# PSU.net
KiCad netlist of a schematic drawn in EAGLE
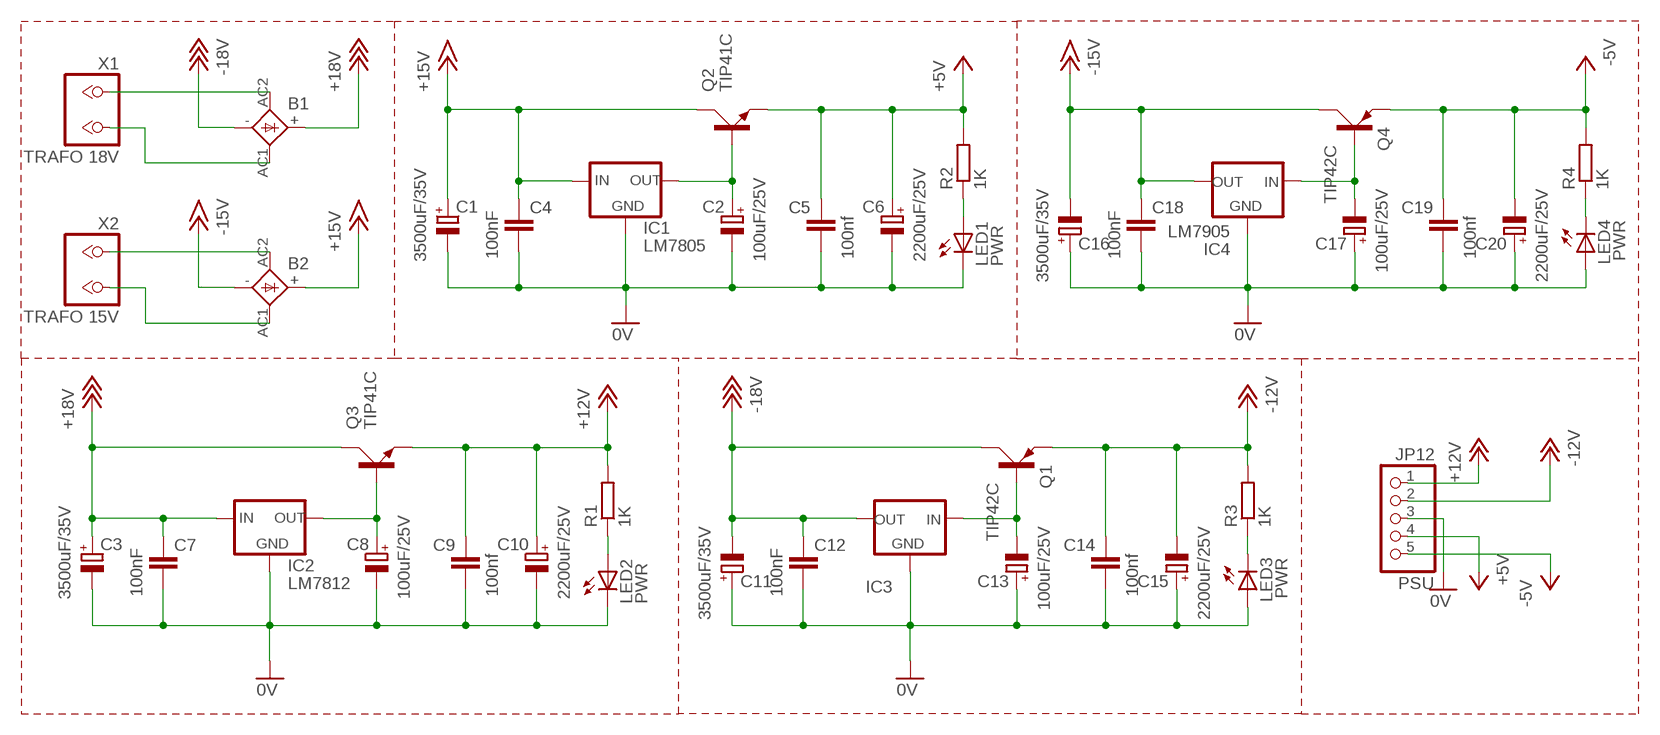
[diagram p0: schematic, sheet 1]

(export (version "E")
  (design (tool "Eeschema 10.0.6"))
  (components
    (comp (ref "B1")
      (value "KBL")
      (footprint "eagle-import:KBL")
      (libsource (lib "eagle-import") (part "KBL"))
    )
    (comp (ref "B2")
      (value "KBL")
      (footprint "eagle-import:KBL")
      (libsource (lib "eagle-import") (part "KBL"))
    )
    (comp (ref "C1")
      (value "3500uF/35V")
      (footprint "eagle-import:EB20D")
      (libsource (lib "eagle-import") (part "CPOL-EUE10-20"))
    )
    (comp (ref "C2")
      (value "100uF/25V")
      (footprint "eagle-import:E2,5-7")
      (libsource (lib "eagle-import") (part "CPOL-EUE2.5-7"))
    )
    (comp (ref "C3")
      (value "3500uF/35V")
      (footprint "eagle-import:EB20D")
      (libsource (lib "eagle-import") (part "CPOL-EUE10-20"))
    )
    (comp (ref "C4")
      (value "100nF")
      (footprint "eagle-import:C050-025X075")
      (libsource (lib "eagle-import") (part "C-EU050-025X075"))
    )
    (comp (ref "C5")
      (value "100nf")
      (footprint "eagle-import:C050-025X075")
      (libsource (lib "eagle-import") (part "C-EU050-025X075"))
    )
    (comp (ref "C6")
      (value "2200uF/25V")
      (footprint "eagle-import:E5-13")
      (libsource (lib "eagle-import") (part "CPOL-EUE5-13"))
    )
    (comp (ref "C7")
      (value "100nF")
      (footprint "eagle-import:C050-025X075")
      (libsource (lib "eagle-import") (part "C-EU050-025X075"))
    )
    (comp (ref "C8")
      (value "100uF/25V")
      (footprint "eagle-import:E2,5-7")
      (libsource (lib "eagle-import") (part "CPOL-EUE2.5-7"))
    )
    (comp (ref "C9")
      (value "100nf")
      (footprint "eagle-import:C050-025X075")
      (libsource (lib "eagle-import") (part "C-EU050-025X075"))
    )
    (comp (ref "C10")
      (value "2200uF/25V")
      (footprint "eagle-import:E5-13")
      (libsource (lib "eagle-import") (part "CPOL-EUE5-13"))
    )
    (comp (ref "C11")
      (value "3500uF/35V")
      (footprint "eagle-import:EB20D")
      (libsource (lib "eagle-import") (part "CPOL-EUE10-20"))
    )
    (comp (ref "C12")
      (value "100nF")
      (footprint "eagle-import:C050-025X075")
      (libsource (lib "eagle-import") (part "C-EU050-025X075"))
    )
    (comp (ref "C13")
      (value "100uF/25V")
      (footprint "eagle-import:E2,5-7")
      (libsource (lib "eagle-import") (part "CPOL-EUE2.5-7"))
    )
    (comp (ref "C14")
      (value "100nf")
      (footprint "eagle-import:C050-025X075")
      (libsource (lib "eagle-import") (part "C-EU050-025X075"))
    )
    (comp (ref "C15")
      (value "2200uF/25V")
      (footprint "eagle-import:E5-13")
      (libsource (lib "eagle-import") (part "CPOL-EUE5-13"))
    )
    (comp (ref "C16")
      (value "3500uF/35V")
      (footprint "eagle-import:EB20D")
      (libsource (lib "eagle-import") (part "CPOL-EUE10-20"))
    )
    (comp (ref "C17")
      (value "100uF/25V")
      (footprint "eagle-import:E2,5-7")
      (libsource (lib "eagle-import") (part "CPOL-EUE2.5-7"))
    )
    (comp (ref "C18")
      (value "100nF")
      (footprint "eagle-import:C050-025X075")
      (libsource (lib "eagle-import") (part "C-EU050-025X075"))
    )
    (comp (ref "C19")
      (value "100nf")
      (footprint "eagle-import:C050-025X075")
      (libsource (lib "eagle-import") (part "C-EU050-025X075"))
    )
    (comp (ref "C20")
      (value "2200uF/25V")
      (footprint "eagle-import:E5-13")
      (libsource (lib "eagle-import") (part "CPOL-EUE5-13"))
    )
    (comp (ref "IC1")
      (value "LM7805")
      (footprint "eagle-import:78XXS")
      (libsource (lib "eagle-import") (part "78XXS"))
    )
    (comp (ref "IC2")
      (value "LM7812")
      (footprint "eagle-import:78XXS")
      (libsource (lib "eagle-import") (part "78XXS"))
    )
    (comp (ref "IC3")
      (value "79XXS")
      (footprint "eagle-import:79XXS")
      (libsource (lib "eagle-import") (part "79XXS"))
    )
    (comp (ref "IC4")
      (value "LM7905")
      (footprint "eagle-import:79XXS")
      (libsource (lib "eagle-import") (part "79XXS"))
    )
    (comp (ref "JP12")
      (value "PSU")
      (footprint "eagle-import:1X05")
      (libsource (lib "eagle-import") (part "PINHD-1X5{dblquote}"))
    )
    (comp (ref "LED1")
      (value "PWR")
      (footprint "eagle-import:LED3MM")
      (libsource (lib "eagle-import") (part "LEDLED3MM"))
    )
    (comp (ref "LED2")
      (value "PWR")
      (footprint "eagle-import:LED3MM")
      (libsource (lib "eagle-import") (part "LEDLED3MM"))
    )
    (comp (ref "LED3")
      (value "PWR")
      (footprint "eagle-import:LED3MM")
      (libsource (lib "eagle-import") (part "LEDLED3MM"))
    )
    (comp (ref "LED4")
      (value "PWR")
      (footprint "eagle-import:LED3MM")
      (libsource (lib "eagle-import") (part "LEDLED3MM"))
    )
    (comp (ref "Q1")
      (value "TIP42C")
      (footprint "eagle-import:TO220AV")
      (libsource (lib "eagle-import") (part "TIP42C"))
    )
    (comp (ref "Q2")
      (value "TIP41C")
      (footprint "eagle-import:TO220AV")
      (libsource (lib "eagle-import") (part "TIP41C"))
    )
    (comp (ref "Q3")
      (value "TIP41C")
      (footprint "eagle-import:TO220AV")
      (libsource (lib "eagle-import") (part "TIP41C"))
    )
    (comp (ref "Q4")
      (value "TIP42C")
      (footprint "eagle-import:TO220AV")
      (libsource (lib "eagle-import") (part "TIP42C"))
    )
    (comp (ref "R1")
      (value "1K")
      (footprint "eagle-import:0207_7")
      (libsource (lib "eagle-import") (part "R-EU_0207/7"))
    )
    (comp (ref "R2")
      (value "1K")
      (footprint "eagle-import:0207_7")
      (libsource (lib "eagle-import") (part "R-EU_0207/7"))
    )
    (comp (ref "R3")
      (value "1K")
      (footprint "eagle-import:0207_7")
      (libsource (lib "eagle-import") (part "R-EU_0207/7"))
    )
    (comp (ref "R4")
      (value "1K")
      (footprint "eagle-import:0207_7")
      (libsource (lib "eagle-import") (part "R-EU_0207/7"))
    )
    (comp (ref "X1")
      (value "TRAFO 18V")
      (footprint "eagle-import:TB2")
      (libsource (lib "eagle-import") (part "2PIN"))
    )
    (comp (ref "X2")
      (value "TRAFO 15V")
      (footprint "eagle-import:TB2")
      (libsource (lib "eagle-import") (part "2PIN"))
    )
  )
  (nets
    (net (code "1") (name "+5V") (class "Default")
      (node (ref "C5") (pin "1") (pinfunction "1_1") (pintype "passive"))
      (node (ref "C6") (pin "+") (pinfunction "+_+") (pintype "passive"))
      (node (ref "JP12") (pin "4") (pinfunction "4_4") (pintype "passive"))
      (node (ref "Q2") (pin "E") (pinfunction "E_E") (pintype "passive"))
      (node (ref "R2") (pin "2") (pinfunction "2_2") (pintype "passive"))
    )
    (net (code "2") (name "+12V") (class "Default")
      (node (ref "C10") (pin "+") (pinfunction "+_+") (pintype "passive"))
      (node (ref "C9") (pin "1") (pinfunction "1_1") (pintype "passive"))
      (node (ref "JP12") (pin "1") (pinfunction "1_1") (pintype "passive"))
      (node (ref "Q3") (pin "E") (pinfunction "E_E") (pintype "passive"))
      (node (ref "R1") (pin "2") (pinfunction "2_2") (pintype "passive"))
    )
    (net (code "3") (name "+15V") (class "Default")
      (node (ref "B2") (pin "+") (pinfunction "+_+") (pintype "passive"))
      (node (ref "C1") (pin "+") (pinfunction "+_+") (pintype "passive"))
      (node (ref "C4") (pin "1") (pinfunction "1_1") (pintype "passive"))
      (node (ref "IC1") (pin "IN") (pinfunction "IN_IN") (pintype "input"))
      (node (ref "Q2") (pin "C") (pinfunction "C_C") (pintype "passive"))
    )
    (net (code "4") (name "+18V") (class "Default")
      (node (ref "B1") (pin "+") (pinfunction "+_+") (pintype "passive"))
      (node (ref "C3") (pin "+") (pinfunction "+_+") (pintype "passive"))
      (node (ref "C7") (pin "1") (pinfunction "1_1") (pintype "passive"))
      (node (ref "IC2") (pin "IN") (pinfunction "IN_IN") (pintype "input"))
      (node (ref "Q3") (pin "C") (pinfunction "C_C") (pintype "passive"))
    )
    (net (code "5") (name "-5V") (class "Default")
      (node (ref "C19") (pin "1") (pinfunction "1_1") (pintype "passive"))
      (node (ref "C20") (pin "-") (pinfunction "-_-") (pintype "passive"))
      (node (ref "JP12") (pin "5") (pinfunction "5_5") (pintype "passive"))
      (node (ref "Q4") (pin "E") (pinfunction "E_E") (pintype "passive"))
      (node (ref "R4") (pin "2") (pinfunction "2_2") (pintype "passive"))
    )
    (net (code "6") (name "-12V") (class "Default")
      (node (ref "C14") (pin "1") (pinfunction "1_1") (pintype "passive"))
      (node (ref "C15") (pin "-") (pinfunction "-_-") (pintype "passive"))
      (node (ref "JP12") (pin "2") (pinfunction "2_2") (pintype "passive"))
      (node (ref "Q1") (pin "E") (pinfunction "E_E") (pintype "passive"))
      (node (ref "R3") (pin "2") (pinfunction "2_2") (pintype "passive"))
    )
    (net (code "7") (name "-15V") (class "Default")
      (node (ref "B2") (pin "-") (pinfunction "-_-") (pintype "passive"))
      (node (ref "C16") (pin "-") (pinfunction "-_-") (pintype "passive"))
      (node (ref "C18") (pin "1") (pinfunction "1_1") (pintype "passive"))
      (node (ref "IC4") (pin "OUT") (pinfunction "OUT_OUT") (pintype "passive"))
      (node (ref "Q4") (pin "C") (pinfunction "C_C") (pintype "passive"))
    )
    (net (code "8") (name "-18V") (class "Default")
      (node (ref "B1") (pin "-") (pinfunction "-_-") (pintype "passive"))
      (node (ref "C11") (pin "-") (pinfunction "-_-") (pintype "passive"))
      (node (ref "C12") (pin "1") (pinfunction "1_1") (pintype "passive"))
      (node (ref "IC3") (pin "OUT") (pinfunction "OUT_OUT") (pintype "passive"))
      (node (ref "Q1") (pin "C") (pinfunction "C_C") (pintype "passive"))
    )
    (net (code "9") (name "0V") (class "Default")
      (node (ref "C1") (pin "-") (pinfunction "-_-") (pintype "passive"))
      (node (ref "C10") (pin "-") (pinfunction "-_-") (pintype "passive"))
      (node (ref "C11") (pin "+") (pinfunction "+_+") (pintype "passive"))
      (node (ref "C12") (pin "2") (pinfunction "2_2") (pintype "passive"))
      (node (ref "C13") (pin "+") (pinfunction "+_+") (pintype "passive"))
      (node (ref "C14") (pin "2") (pinfunction "2_2") (pintype "passive"))
      (node (ref "C15") (pin "+") (pinfunction "+_+") (pintype "passive"))
      (node (ref "C16") (pin "+") (pinfunction "+_+") (pintype "passive"))
      (node (ref "C17") (pin "+") (pinfunction "+_+") (pintype "passive"))
      (node (ref "C18") (pin "2") (pinfunction "2_2") (pintype "passive"))
      (node (ref "C19") (pin "2") (pinfunction "2_2") (pintype "passive"))
      (node (ref "C2") (pin "-") (pinfunction "-_-") (pintype "passive"))
      (node (ref "C20") (pin "+") (pinfunction "+_+") (pintype "passive"))
      (node (ref "C3") (pin "-") (pinfunction "-_-") (pintype "passive"))
      (node (ref "C4") (pin "2") (pinfunction "2_2") (pintype "passive"))
      (node (ref "C5") (pin "2") (pinfunction "2_2") (pintype "passive"))
      (node (ref "C6") (pin "-") (pinfunction "-_-") (pintype "passive"))
      (node (ref "C7") (pin "2") (pinfunction "2_2") (pintype "passive"))
      (node (ref "C8") (pin "-") (pinfunction "-_-") (pintype "passive"))
      (node (ref "C9") (pin "2") (pinfunction "2_2") (pintype "passive"))
      (node (ref "IC1") (pin "GND") (pinfunction "GND_GND") (pintype "input"))
      (node (ref "IC2") (pin "GND") (pinfunction "GND_GND") (pintype "input"))
      (node (ref "IC3") (pin "GND") (pinfunction "GND_GND") (pintype "input"))
      (node (ref "IC4") (pin "GND") (pinfunction "GND_GND") (pintype "input"))
      (node (ref "JP12") (pin "3") (pinfunction "3_3") (pintype "passive"))
      (node (ref "LED1") (pin "K") (pinfunction "C_K") (pintype "passive"))
      (node (ref "LED2") (pin "K") (pinfunction "C_K") (pintype "passive"))
      (node (ref "LED3") (pin "A") (pinfunction "A_A") (pintype "passive"))
      (node (ref "LED4") (pin "A") (pinfunction "A_A") (pintype "passive"))
    )
    (net (code "10") (name "Net-(B1-AC1)") (class "Default")
      (node (ref "B1") (pin "AC2") (pinfunction "AC1_AC2") (pintype "passive"))
      (node (ref "X1") (pin "1") (pinfunction "1_1") (pintype "bidirectional"))
    )
    (net (code "11") (name "Net-(B1-AC2)") (class "Default")
      (node (ref "B1") (pin "AC1") (pinfunction "AC2_AC1") (pintype "passive"))
      (node (ref "X1") (pin "2") (pinfunction "2_2") (pintype "bidirectional"))
    )
    (net (code "12") (name "Net-(B2-AC1)") (class "Default")
      (node (ref "B2") (pin "AC2") (pinfunction "AC1_AC2") (pintype "passive"))
      (node (ref "X2") (pin "1") (pinfunction "1_1") (pintype "bidirectional"))
    )
    (net (code "13") (name "Net-(B2-AC2)") (class "Default")
      (node (ref "B2") (pin "AC1") (pinfunction "AC2_AC1") (pintype "passive"))
      (node (ref "X2") (pin "2") (pinfunction "2_2") (pintype "bidirectional"))
    )
    (net (code "14") (name "Net-(C2-Pad+)") (class "Default")
      (node (ref "C2") (pin "+") (pinfunction "+_+") (pintype "passive"))
      (node (ref "IC1") (pin "OUT") (pinfunction "OUT_OUT") (pintype "passive"))
      (node (ref "Q2") (pin "B") (pinfunction "B_B") (pintype "passive"))
    )
    (net (code "15") (name "Net-(C8-Pad+)") (class "Default")
      (node (ref "C8") (pin "+") (pinfunction "+_+") (pintype "passive"))
      (node (ref "IC2") (pin "OUT") (pinfunction "OUT_OUT") (pintype "passive"))
      (node (ref "Q3") (pin "B") (pinfunction "B_B") (pintype "passive"))
    )
    (net (code "16") (name "Net-(C13-Pad-)") (class "Default")
      (node (ref "C13") (pin "-") (pinfunction "-_-") (pintype "passive"))
      (node (ref "IC3") (pin "IN") (pinfunction "IN_IN") (pintype "input"))
      (node (ref "Q1") (pin "B") (pinfunction "B_B") (pintype "passive"))
    )
    (net (code "17") (name "Net-(C17-Pad-)") (class "Default")
      (node (ref "C17") (pin "-") (pinfunction "-_-") (pintype "passive"))
      (node (ref "IC4") (pin "IN") (pinfunction "IN_IN") (pintype "input"))
      (node (ref "Q4") (pin "B") (pinfunction "B_B") (pintype "passive"))
    )
    (net (code "18") (name "Net-(LED1-PadA)") (class "Default")
      (node (ref "LED1") (pin "A") (pinfunction "A_A") (pintype "passive"))
      (node (ref "R2") (pin "1") (pinfunction "1_1") (pintype "passive"))
    )
    (net (code "19") (name "Net-(LED2-PadA)") (class "Default")
      (node (ref "LED2") (pin "A") (pinfunction "A_A") (pintype "passive"))
      (node (ref "R1") (pin "1") (pinfunction "1_1") (pintype "passive"))
    )
    (net (code "20") (name "Net-(LED3-C)") (class "Default")
      (node (ref "LED3") (pin "K") (pinfunction "C_K") (pintype "passive"))
      (node (ref "R3") (pin "1") (pinfunction "1_1") (pintype "passive"))
    )
    (net (code "21") (name "Net-(LED4-C)") (class "Default")
      (node (ref "LED4") (pin "K") (pinfunction "C_K") (pintype "passive"))
      (node (ref "R4") (pin "1") (pinfunction "1_1") (pintype "passive"))
    )
  )
)
